# Top.net
KiCad netlist of a schematic drawn in Altium Designer
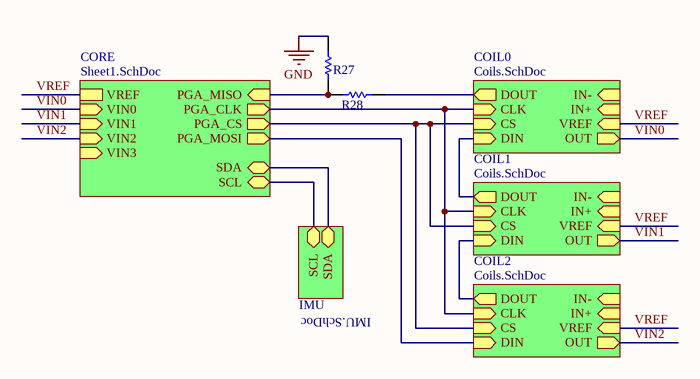
[diagram p0: Top.SchDoc]

(export (version "E")
  (design (tool "Eeschema 10.0.6"))
  (components
    (comp (ref "R27")
      (value "10K 1% 0402(1005)")
      (footprint "RESC0402(1005)_N")
      (description "10K 0.063W 1% 0402 (1005 Metric)  SMD")
      (fields (field (name "TOLERANCE") "1 %") (field (name "POWER") "0.063 W"))
      (libsource (lib "Altium Content Vault") (part "CMP-1011-00623-1"))
    )
    (comp (ref "R28")
      (value "5K6 5% 0402(1005)")
      (footprint "RESC0402(1005)_N")
      (description "5K6 0.063W 5% 0402 (1005 Metric)  SMD")
      (fields (field (name "TOLERANCE") "5 %") (field (name "POWER") "0.063 W"))
      (libsource (lib "Altium Content Vault") (part "CMP-1011-00092-1"))
    )
  )
  (nets
    (net (code "2") (name "/DOUT_1") (class "Default")
      (node (ref "R28") (pin "2") (pinfunction "2_2") (pintype "passive"))
    )
    (net (code "12") (name "/PGA_MISO") (class "Default")
      (node (ref "R27") (pin "2") (pinfunction "2_2") (pintype "passive"))
      (node (ref "R28") (pin "1") (pinfunction "1_1") (pintype "passive"))
    )
    (net (code "21") (name "GND") (class "Default")
      (node (ref "R27") (pin "1") (pinfunction "1_1") (pintype "passive"))
    )
  )
)
